# JTAG20_TO_JTAG10.net
KiCad netlist of a schematic drawn in Altium Designer
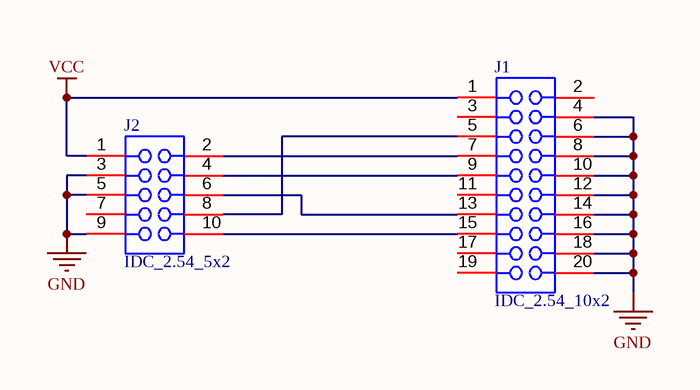
[diagram p0: JTAG20_TO_JTAG10.SchDoc]

(export (version "E")
  (design (tool "Eeschema 10.0.6"))
  (components
    (comp (ref "J1")
      (value "IDC_2.54_10x2")
      (footprint "IDC_CONNECTOR_20_2.54")
      (libsource (lib "Lib31082020") (part "IDC_2.54_10x2"))
    )
    (comp (ref "J2")
      (value "IDC_2.54_5x2")
      (footprint "IDC_CONNECTOR_10x2.54")
      (libsource (lib "Lib31082020") (part "IDC_2.54_5x2"))
    )
  )
  (nets
    (net (code "1") (name "GND") (class "Default")
      (node (ref "J1") (pin "10") (pinfunction "10_10") (pintype "passive"))
      (node (ref "J1") (pin "12") (pinfunction "12_12") (pintype "passive"))
      (node (ref "J1") (pin "14") (pinfunction "14_14") (pintype "passive"))
      (node (ref "J1") (pin "16") (pinfunction "16_16") (pintype "passive"))
      (node (ref "J1") (pin "18") (pinfunction "18_18") (pintype "passive"))
      (node (ref "J1") (pin "20") (pinfunction "20_20") (pintype "passive"))
      (node (ref "J1") (pin "4") (pinfunction "4_4") (pintype "passive"))
      (node (ref "J1") (pin "6") (pinfunction "6_6") (pintype "passive"))
      (node (ref "J1") (pin "8") (pinfunction "8_8") (pintype "passive"))
      (node (ref "J2") (pin "3") (pinfunction "3_3") (pintype "passive"))
      (node (ref "J2") (pin "5") (pinfunction "5_5") (pintype "passive"))
      (node (ref "J2") (pin "9") (pinfunction "9_9") (pintype "passive"))
    )
    (net (code "2") (name "Net-(J1-Pad5)") (class "Default")
      (node (ref "J1") (pin "5") (pinfunction "5_5") (pintype "passive"))
      (node (ref "J2") (pin "8") (pinfunction "8_8") (pintype "passive"))
    )
    (net (code "3") (name "Net-(J1-Pad7)") (class "Default")
      (node (ref "J1") (pin "7") (pinfunction "7_7") (pintype "passive"))
      (node (ref "J2") (pin "2") (pinfunction "2_2") (pintype "passive"))
    )
    (net (code "4") (name "Net-(J1-Pad9)") (class "Default")
      (node (ref "J1") (pin "9") (pinfunction "9_9") (pintype "passive"))
      (node (ref "J2") (pin "4") (pinfunction "4_4") (pintype "passive"))
    )
    (net (code "5") (name "Net-(J1-Pad13)") (class "Default")
      (node (ref "J1") (pin "13") (pinfunction "13_13") (pintype "passive"))
      (node (ref "J2") (pin "6") (pinfunction "6_6") (pintype "passive"))
    )
    (net (code "6") (name "Net-(J1-Pad15)") (class "Default")
      (node (ref "J1") (pin "15") (pinfunction "15_15") (pintype "passive"))
      (node (ref "J2") (pin "10") (pinfunction "10_10") (pintype "passive"))
    )
    (net (code "7") (name "VCC") (class "Default")
      (node (ref "J1") (pin "1") (pinfunction "1_1") (pintype "passive"))
      (node (ref "J2") (pin "1") (pinfunction "1_1") (pintype "passive"))
    )
    (net (code "8") (name "unconnected-(J1-Pad2)") (class "Default")
      (node (ref "J1") (pin "2") (pinfunction "2_2") (pintype "passive"))
    )
    (net (code "9") (name "unconnected-(J1-Pad3)") (class "Default")
      (node (ref "J1") (pin "3") (pinfunction "3_3") (pintype "passive"))
    )
    (net (code "10") (name "unconnected-(J1-Pad11)") (class "Default")
      (node (ref "J1") (pin "11") (pinfunction "11_11") (pintype "passive"))
    )
    (net (code "11") (name "unconnected-(J1-Pad17)") (class "Default")
      (node (ref "J1") (pin "17") (pinfunction "17_17") (pintype "passive"))
    )
    (net (code "12") (name "unconnected-(J1-Pad19)") (class "Default")
      (node (ref "J1") (pin "19") (pinfunction "19_19") (pintype "passive"))
    )
    (net (code "13") (name "unconnected-(J2-Pad7)") (class "Default")
      (node (ref "J2") (pin "7") (pinfunction "7_7") (pintype "passive"))
    )
  )
)
